# Driver_Morpheus_SENSOR_CORRENTE.net
KiCad netlist of a schematic drawn in Altium Designer
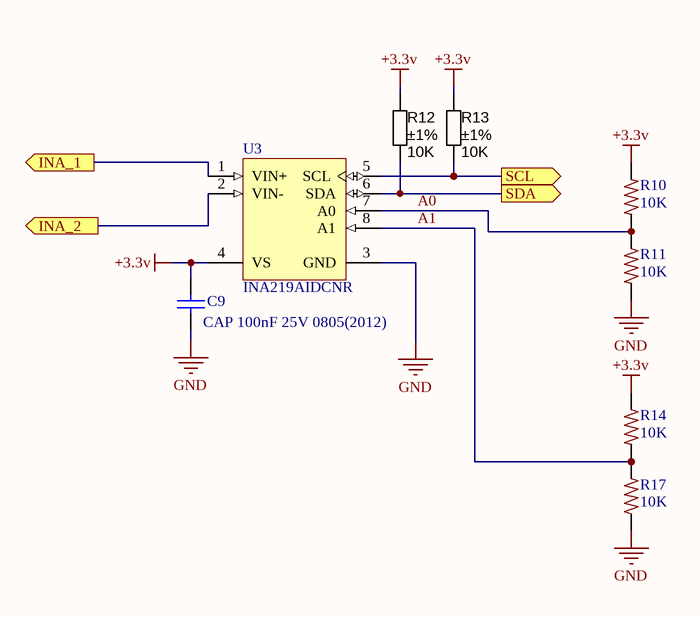
[diagram p0: Driver Morpheus SENSOR CORRENTE.SchDoc]

(export (version "E")
  (design (tool "Eeschema 10.0.6"))
  (components
    (comp (ref "C9")
      (value "CAP 100nF 25V 0805(2012)")
      (footprint "CAPC0805(2012)145_M")
      (description "CAP 100nF 25V ±5% 0805 (2012 Metric) Thickness 1.45mm SMD")
      (fields (field (name "TOLERANCE") "Â±5%"))
      (libsource (lib "Altium Content Vault") (part "CAP"))
    )
    (comp (ref "R10")
      (value "10K")
      (footprint "0402-RES-HD")
      (description "RES 10K OHM 1/10W 1% 0402 SMD")
      (fields (field (name "PART NO") "ERJ-2RKF1002X"))
      (libsource (lib "IMBEL") (part "RESISTOR"))
    )
    (comp (ref "R11")
      (value "10K")
      (footprint "0402-RES-HD")
      (description "RES 10K OHM 1/10W 1% 0402 SMD")
      (fields (field (name "PART NO") "ERJ-2RKF1002X"))
      (libsource (lib "IMBEL") (part "RESISTOR"))
    )
    (comp (ref "R12")
      (value "10K")
      (footprint "RESC1608X55N")
      (description "Resistor SMD chip 10k Ohm 0.1W 1% 0603")
      (fields (field (name "TOLERANCE") "±1%") (field (name "Comment") "Thick Film"))
      (libsource (lib "PBL - Resistors") (part "RES_10K_0603_1%"))
    )
    (comp (ref "R13")
      (value "10K")
      (footprint "RESC1608X55N")
      (description "Resistor SMD chip 10k Ohm 0.1W 1% 0603")
      (fields (field (name "TOLERANCE") "±1%") (field (name "Comment") "Thick Film"))
      (libsource (lib "PBL - Resistors") (part "RES_10K_0603_1%"))
    )
    (comp (ref "R14")
      (value "10K")
      (footprint "0402-RES-HD")
      (description "RES 10K OHM 1/10W 1% 0402 SMD")
      (fields (field (name "PART NO") "ERJ-2RKF1002X"))
      (libsource (lib "IMBEL") (part "RESISTOR"))
    )
    (comp (ref "R17")
      (value "10K")
      (footprint "0402-RES-HD")
      (description "RES 10K OHM 1/10W 1% 0402 SMD")
      (fields (field (name "PART NO") "ERJ-2RKF1002X"))
      (libsource (lib "IMBEL") (part "RESISTOR"))
    )
    (comp (ref "U3")
      (value "INA219AIDCNR")
      (footprint "DCN0008A_M")
      (fields (field (name "MANUFACTURER") "Texas Instruments"))
      (libsource (lib "Altium Content Vault") (part "TI-INA219DCN8"))
    )
  )
  (nets
    (net (code "1") (name "+3.3v") (class "Default")
      (node (ref "C9") (pin "2") (pinfunction "2_2") (pintype "passive"))
      (node (ref "R10") (pin "2") (pinfunction "2_2") (pintype "passive"))
      (node (ref "R12") (pin "1") (pinfunction "1_1") (pintype "passive"))
      (node (ref "R13") (pin "1") (pinfunction "1_1") (pintype "passive"))
      (node (ref "R14") (pin "2") (pinfunction "2_2") (pintype "passive"))
      (node (ref "U3") (pin "4") (pinfunction "VS_4") (pintype "power_in"))
    )
    (net (code "2") (name "/A0") (class "Default")
      (node (ref "R10") (pin "1") (pinfunction "1_1") (pintype "passive"))
      (node (ref "R11") (pin "2") (pinfunction "2_2") (pintype "passive"))
      (node (ref "U3") (pin "7") (pinfunction "A0_7") (pintype "input"))
    )
    (net (code "3") (name "/A1") (class "Default")
      (node (ref "R14") (pin "1") (pinfunction "1_1") (pintype "passive"))
      (node (ref "R17") (pin "2") (pinfunction "2_2") (pintype "passive"))
      (node (ref "U3") (pin "8") (pinfunction "A1_8") (pintype "input"))
    )
    (net (code "4") (name "/INA_1") (class "Default")
      (node (ref "U3") (pin "1") (pinfunction "VIN+_1") (pintype "input"))
    )
    (net (code "5") (name "/INA_2") (class "Default")
      (node (ref "U3") (pin "2") (pinfunction "VIN-_2") (pintype "input"))
    )
    (net (code "6") (name "/SCL") (class "Default")
      (node (ref "R13") (pin "2") (pinfunction "2_2") (pintype "passive"))
      (node (ref "U3") (pin "5") (pinfunction "SCL_5") (pintype "bidirectional"))
    )
    (net (code "7") (name "/SDA") (class "Default")
      (node (ref "R12") (pin "2") (pinfunction "2_2") (pintype "passive"))
      (node (ref "U3") (pin "6") (pinfunction "SDA_6") (pintype "bidirectional"))
    )
    (net (code "8") (name "GND") (class "Default")
      (node (ref "C9") (pin "1") (pinfunction "1_1") (pintype "passive"))
      (node (ref "R11") (pin "1") (pinfunction "1_1") (pintype "passive"))
      (node (ref "R17") (pin "1") (pinfunction "1_1") (pintype "passive"))
      (node (ref "U3") (pin "3") (pinfunction "GND_3") (pintype "power_in"))
    )
  )
)
